# light_switch_smd3_fork.net
KiCad netlist of a schematic drawn in EAGLE
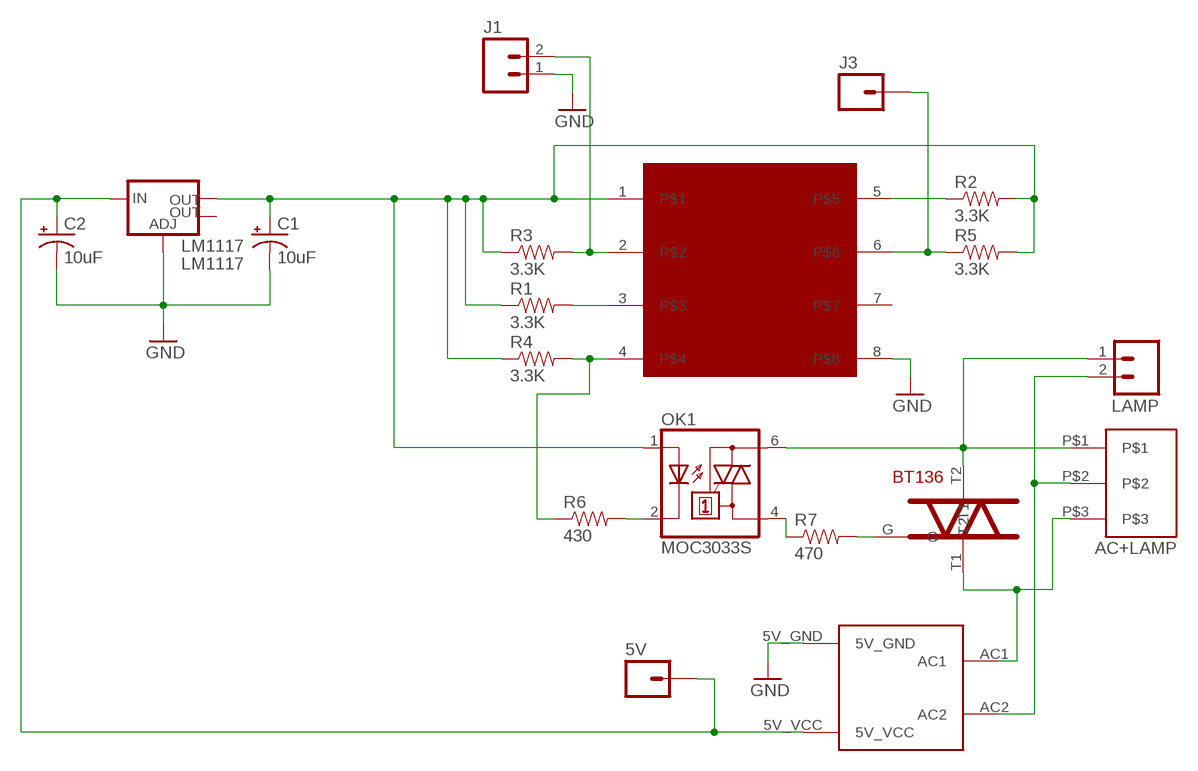
[diagram p0: schematic, sheet 1]

(export (version "E")
  (design (tool "Eeschema 10.0.6"))
  (components
    (comp (ref "5V")
      (value "M01PTH")
      (footprint "eagle-import:1X01")
      (libsource (lib "eagle-import") (part "M01PTH"))
    )
    (comp (ref "AC+LAMP")
      (value "DG350-3.5-03P")
      (footprint "eagle-import:DG350-3.5-03P")
      (libsource (lib "eagle-import") (part "DG350-3.5-03P"))
    )
    (comp (ref "BT136")
      (value "BT136")
      (footprint "eagle-import:BT136-PKG")
      (libsource (lib "eagle-import") (part "BT136"))
    )
    (comp (ref "C1")
      (value "10uF")
      (footprint "eagle-import:0603-POL")
      (libsource (lib "eagle-import") (part "10UF-6.3V-20%(0603)(TANT){dblquote}"))
    )
    (comp (ref "C2")
      (value "10uF")
      (footprint "eagle-import:0603-POL")
      (libsource (lib "eagle-import") (part "10UF-6.3V-20%(0603)(TANT){dblquote}"))
    )
    (comp (ref "J1")
      (value "M02PTH")
      (footprint "eagle-import:1X02")
      (libsource (lib "eagle-import") (part "M02PTH"))
    )
    (comp (ref "J3")
      (value "M01PTH")
      (footprint "eagle-import:1X01")
      (libsource (lib "eagle-import") (part "M01PTH"))
    )
    (comp (ref "LAMP")
      (value "M02PTH")
      (footprint "eagle-import:1X02")
      (libsource (lib "eagle-import") (part "M02PTH"))
    )
    (comp (ref "LM1117")
      (value "LM1117")
      (footprint "eagle-import:SOT223")
      (libsource (lib "eagle-import") (part "V_REG_LM1117SOT223"))
    )
    (comp (ref "OK1")
      (value "MOC3033S")
      (footprint "eagle-import:DIL6-SMD")
      (fields (field (name "MF") "FAIRCHILD SEMICONDUCTOR") (field (name "MPN") "MOC3033S-M"))
      (libsource (lib "eagle-import") (part "MOC30S33"))
    )
    (comp (ref "R1")
      (value "3.3K")
      (footprint "eagle-import:0603-RES")
      (libsource (lib "eagle-import") (part "3.3MOHM-1/10W-1%(0603)"))
    )
    (comp (ref "R2")
      (value "3.3K")
      (footprint "eagle-import:0603-RES")
      (libsource (lib "eagle-import") (part "3.3MOHM-1/10W-1%(0603)"))
    )
    (comp (ref "R3")
      (value "3.3K")
      (footprint "eagle-import:0603-RES")
      (libsource (lib "eagle-import") (part "3.3MOHM-1/10W-1%(0603)"))
    )
    (comp (ref "R4")
      (value "3.3K")
      (footprint "eagle-import:0603-RES")
      (libsource (lib "eagle-import") (part "3.3MOHM-1/10W-1%(0603)"))
    )
    (comp (ref "R5")
      (value "3.3K")
      (footprint "eagle-import:0603-RES")
      (libsource (lib "eagle-import") (part "3.3MOHM-1/10W-1%(0603)"))
    )
    (comp (ref "R6")
      (value "430")
      (footprint "eagle-import:0603-RES")
      (libsource (lib "eagle-import") (part "RESISTOR0603"))
    )
    (comp (ref "R7")
      (value "470")
      (footprint "eagle-import:0603-RES")
      (libsource (lib "eagle-import") (part "RESISTOR0603"))
    )
    (comp (ref "U$1")
      (value "HI-LINK5V-ACDC")
      (footprint "eagle-import:AC5V")
      (libsource (lib "eagle-import") (part "HI-LINK5V-ACDC"))
    )
    (comp (ref "U$2")
      (value "ESP8266-01")
      (footprint "eagle-import:ESP8266-01")
      (libsource (lib "eagle-import") (part "ESP8266-01"))
    )
  )
  (nets
    (net (code "1") (name "GND") (class "Default")
      (node (ref "C1") (pin "K") (pinfunction "-_K") (pintype "passive"))
      (node (ref "C2") (pin "K") (pinfunction "-_K") (pintype "passive"))
      (node (ref "J1") (pin "1") (pinfunction "1_1") (pintype "passive"))
      (node (ref "LM1117") (pin "1") (pinfunction "ADJ_1") (pintype "input"))
      (node (ref "U$1") (pin "5V_GND") (pinfunction "5V_GND_5V_GND") (pintype "bidirectional"))
      (node (ref "U$2") (pin "8") (pinfunction "P$8_8") (pintype "bidirectional"))
    )
    (net (code "2") (name "Net-(AC+LAMP-PadP$2)") (class "Default")
      (node (ref "AC+LAMP") (pin "P$2") (pinfunction "P$2_P$2") (pintype "bidirectional"))
      (node (ref "LAMP") (pin "2") (pinfunction "2_2") (pintype "passive"))
      (node (ref "U$1") (pin "AC2") (pinfunction "AC2_AC2") (pintype "bidirectional"))
    )
    (net (code "3") (name "Net-(AC+LAMP-PadP$3)") (class "Default")
      (node (ref "AC+LAMP") (pin "P$3") (pinfunction "P$3_P$3") (pintype "bidirectional"))
      (node (ref "BT136") (pin "T1") (pinfunction "T1_T1") (pintype "bidirectional"))
      (node (ref "U$1") (pin "AC1") (pinfunction "AC1_AC1") (pintype "bidirectional"))
    )
    (net (code "4") (name "Net-(BT136-PadG)") (class "Default")
      (node (ref "BT136") (pin "G") (pinfunction "G_G") (pintype "bidirectional"))
      (node (ref "R7") (pin "2") (pinfunction "2_2") (pintype "passive"))
    )
    (net (code "5") (name "Net-(C1-+)") (class "Default")
      (node (ref "C1") (pin "A") (pinfunction "+_A") (pintype "passive"))
      (node (ref "LM1117") (pin "2") (pinfunction "OUT_2") (pintype "output"))
      (node (ref "OK1") (pin "1") (pinfunction "A_1") (pintype "passive"))
      (node (ref "R1") (pin "1") (pinfunction "1_1") (pintype "passive"))
      (node (ref "R2") (pin "2") (pinfunction "2_2") (pintype "passive"))
      (node (ref "R3") (pin "1") (pinfunction "1_1") (pintype "passive"))
      (node (ref "R4") (pin "1") (pinfunction "1_1") (pintype "passive"))
      (node (ref "R5") (pin "2") (pinfunction "2_2") (pintype "passive"))
      (node (ref "U$2") (pin "1") (pinfunction "P$1_1") (pintype "bidirectional"))
    )
    (net (code "6") (name "Net-(C2-+)") (class "Default")
      (node (ref "5V") (pin "1") (pinfunction "1_1") (pintype "passive"))
      (node (ref "C2") (pin "A") (pinfunction "+_A") (pintype "passive"))
      (node (ref "LM1117") (pin "3") (pinfunction "IN_3") (pintype "input"))
      (node (ref "U$1") (pin "5V_VCC") (pinfunction "5V_VCC_5V_VCC") (pintype "bidirectional"))
    )
    (net (code "7") (name "Net-(OK1-A1)") (class "Default")
      (node (ref "OK1") (pin "4") (pinfunction "A1_4") (pintype "passive"))
      (node (ref "R7") (pin "1") (pinfunction "1_1") (pintype "passive"))
    )
    (net (code "8") (name "Net-(OK1-A2)") (class "Default")
      (node (ref "AC+LAMP") (pin "P$1") (pinfunction "P$1_P$1") (pintype "bidirectional"))
      (node (ref "BT136") (pin "T2") (pinfunction "T2_T2") (pintype "bidirectional"))
      (node (ref "LAMP") (pin "1") (pinfunction "1_1") (pintype "passive"))
      (node (ref "OK1") (pin "6") (pinfunction "A2_6") (pintype "passive"))
    )
    (net (code "9") (name "Net-(OK1-C)") (class "Default")
      (node (ref "OK1") (pin "2") (pinfunction "C_2") (pintype "passive"))
      (node (ref "R6") (pin "2") (pinfunction "2_2") (pintype "passive"))
    )
    (net (code "10") (name "Net-(U$2-P$2)") (class "Default")
      (node (ref "J1") (pin "2") (pinfunction "2_2") (pintype "passive"))
      (node (ref "R3") (pin "2") (pinfunction "2_2") (pintype "passive"))
      (node (ref "U$2") (pin "2") (pinfunction "P$2_2") (pintype "bidirectional"))
    )
    (net (code "11") (name "Net-(U$2-P$3)") (class "Default")
      (node (ref "R1") (pin "2") (pinfunction "2_2") (pintype "passive"))
      (node (ref "U$2") (pin "3") (pinfunction "P$3_3") (pintype "bidirectional"))
    )
    (net (code "12") (name "Net-(U$2-P$4)") (class "Default")
      (node (ref "R4") (pin "2") (pinfunction "2_2") (pintype "passive"))
      (node (ref "R6") (pin "1") (pinfunction "1_1") (pintype "passive"))
      (node (ref "U$2") (pin "4") (pinfunction "P$4_4") (pintype "bidirectional"))
    )
    (net (code "13") (name "Net-(U$2-P$5)") (class "Default")
      (node (ref "R2") (pin "1") (pinfunction "1_1") (pintype "passive"))
      (node (ref "U$2") (pin "5") (pinfunction "P$5_5") (pintype "bidirectional"))
    )
    (net (code "14") (name "Net-(U$2-P$6)") (class "Default")
      (node (ref "J3") (pin "1") (pinfunction "1_1") (pintype "passive"))
      (node (ref "R5") (pin "1") (pinfunction "1_1") (pintype "passive"))
      (node (ref "U$2") (pin "6") (pinfunction "P$6_6") (pintype "bidirectional"))
    )
    (net (code "15") (name "unconnected-(LM1117-OUT-Pad4)") (class "Default")
      (node (ref "LM1117") (pin "4") (pinfunction "OUT_4") (pintype "output"))
    )
    (net (code "16") (name "unconnected-(U$2-P$7-Pad7)") (class "Default")
      (node (ref "U$2") (pin "7") (pinfunction "P$7_7") (pintype "bidirectional"))
    )
  )
)
